# 5_ButtonsAndLeds.net
KiCad netlist of a schematic drawn in Altium Designer
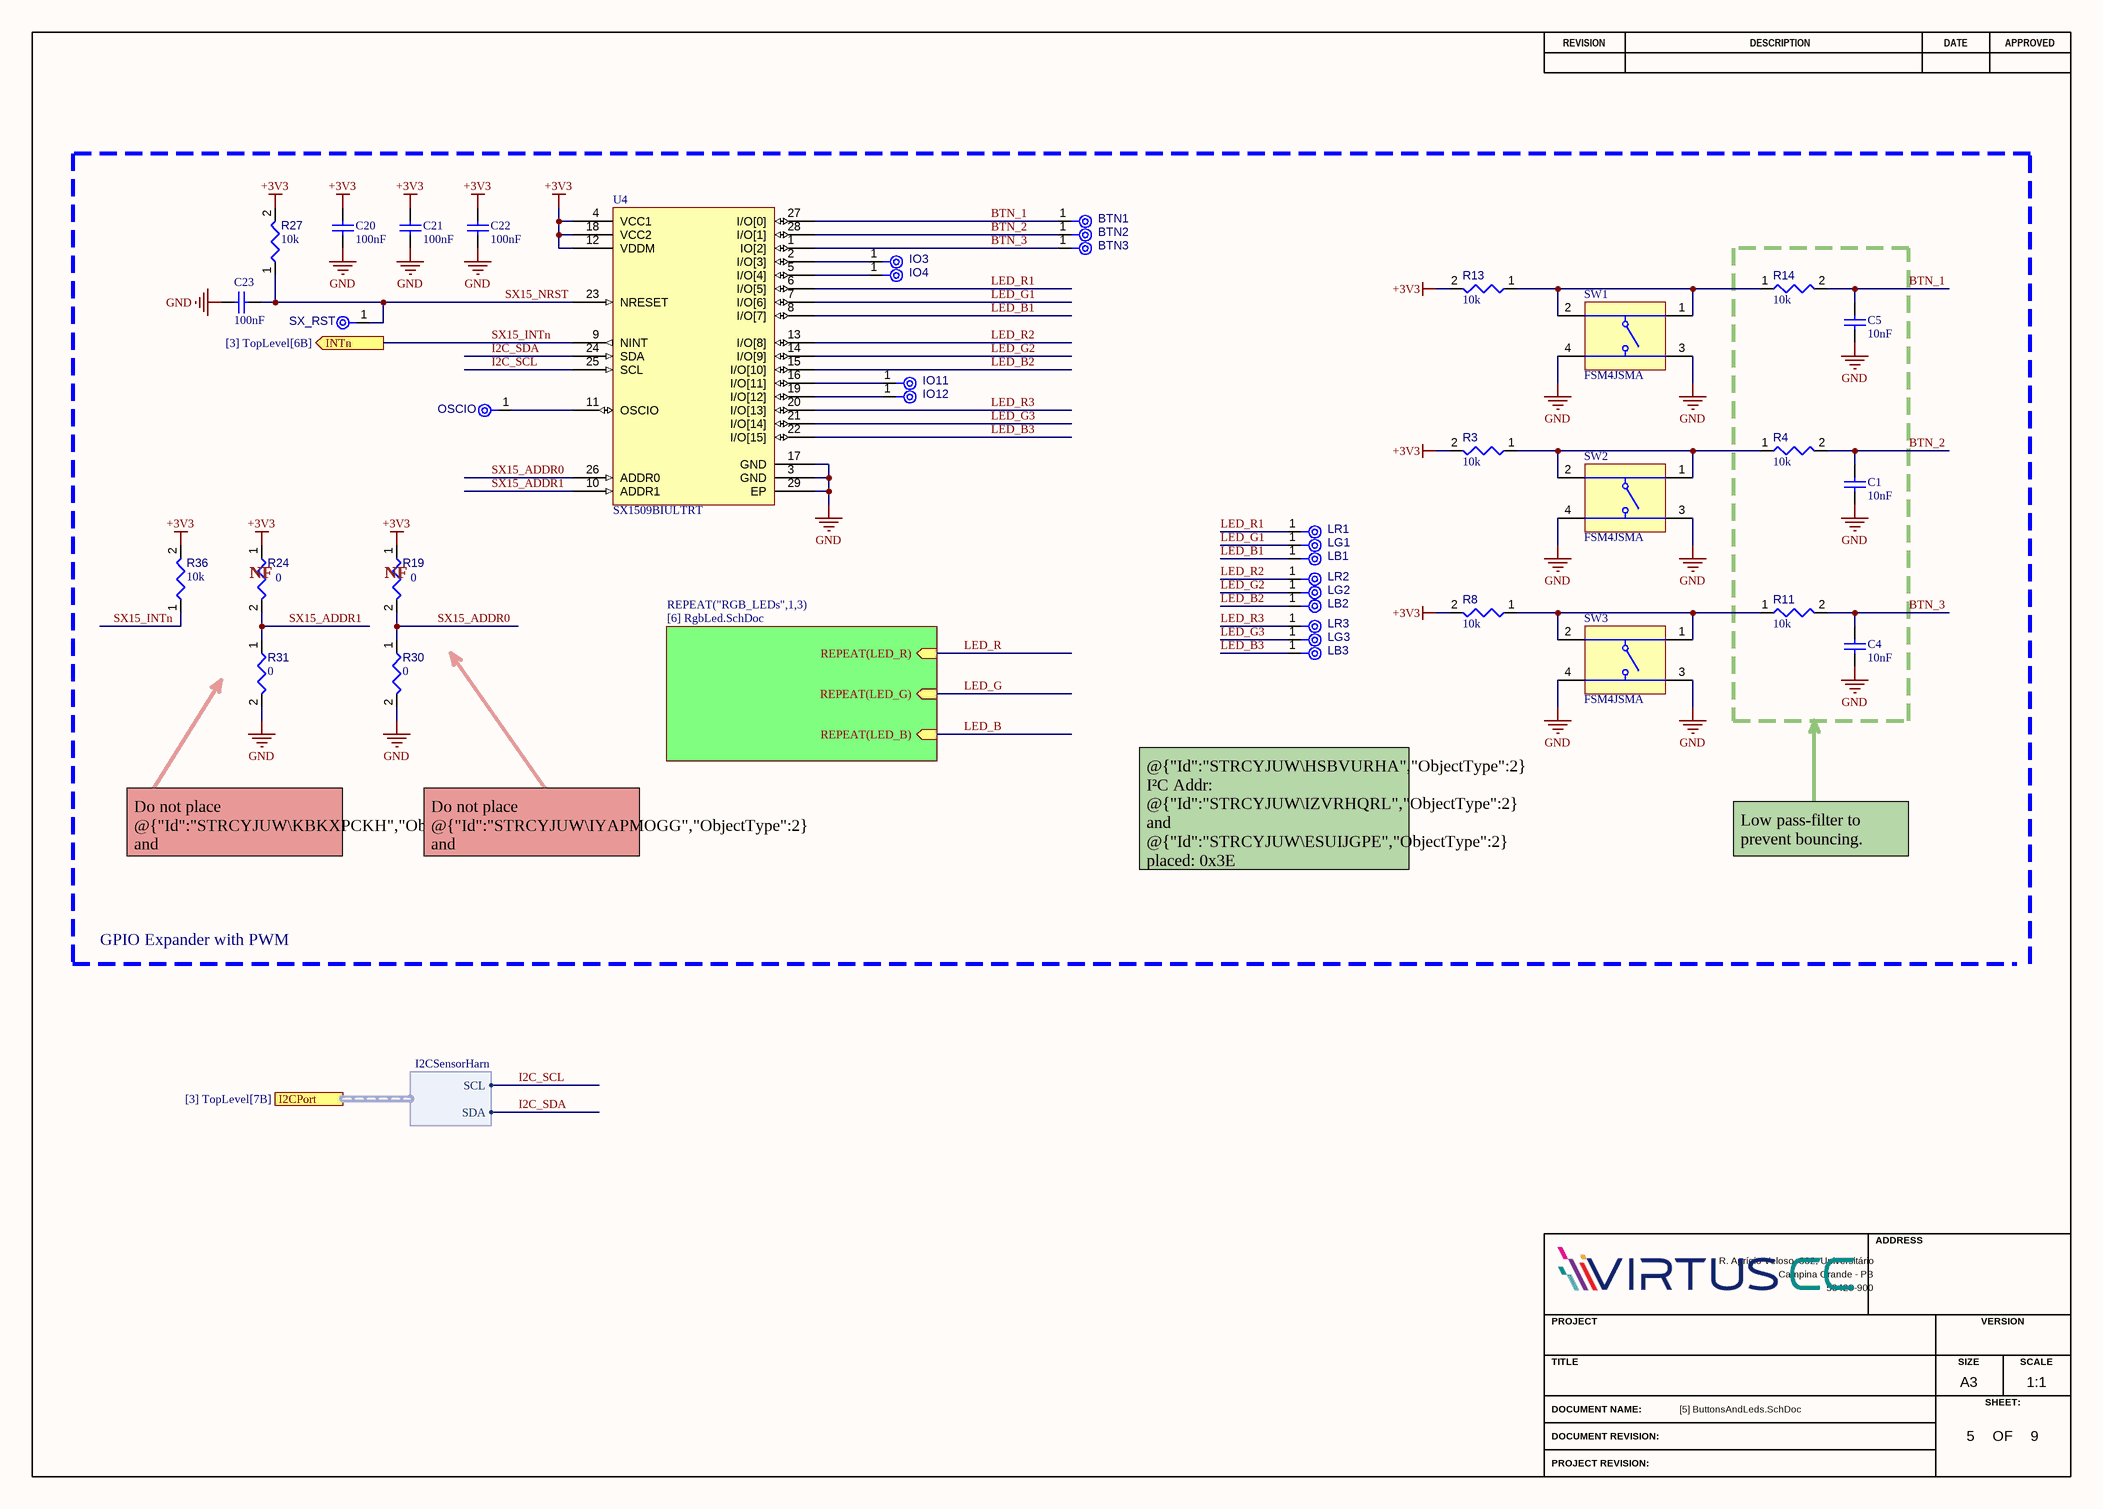
[diagram p0: [5] ButtonsAndLeds.SchDoc]

(export (version "E")
  (design (tool "Eeschema 10.0.6"))
  (components
    (comp (ref "BTN1")
      (value "TPAD6R")
      (footprint "TP06R")
      (description "0.6mm round")
      (libsource (lib "UFCG - Universidade Federal de Campina Grande") (part "CMP-001-0001-4"))
    )
    (comp (ref "BTN2")
      (value "TPAD6R")
      (footprint "TP06R")
      (description "0.6mm round")
      (libsource (lib "UFCG - Universidade Federal de Campina Grande") (part "CMP-001-0001-4"))
    )
    (comp (ref "BTN3")
      (value "TPAD6R")
      (footprint "TP06R")
      (description "0.6mm round")
      (libsource (lib "UFCG - Universidade Federal de Campina Grande") (part "CMP-001-0001-4"))
    )
    (comp (ref "C1")
      (value "10nF")
      (footprint "CAPC0603(1608)100_L")
      (description "Multilayer Ceramic Capacitor, 0.01 uF, 50 V, ± 10%, X7R, 0603 [1608 Metric]")
      (fields (field (name "VOLTAGE") "50V") (field (name "TOLERANCE") "10%"))
      (libsource (lib "UFCG - Universidade Federal de Campina Grande") (part "CAP"))
    )
    (comp (ref "C4")
      (value "10nF")
      (footprint "CAPC0603(1608)100_L")
      (description "Multilayer Ceramic Capacitor, 0.01 uF, 50 V, ± 10%, X7R, 0603 [1608 Metric]")
      (fields (field (name "VOLTAGE") "50V") (field (name "TOLERANCE") "10%"))
      (libsource (lib "UFCG - Universidade Federal de Campina Grande") (part "CAP"))
    )
    (comp (ref "C5")
      (value "10nF")
      (footprint "CAPC0603(1608)100_L")
      (description "Multilayer Ceramic Capacitor, 0.01 uF, 50 V, ± 10%, X7R, 0603 [1608 Metric]")
      (fields (field (name "VOLTAGE") "50V") (field (name "TOLERANCE") "10%"))
      (libsource (lib "UFCG - Universidade Federal de Campina Grande") (part "CAP"))
    )
    (comp (ref "C20")
      (value "100nF")
      (footprint "CAPC0603(1608)100_L")
      (description "Multilayer Ceramic Capacitor, 0.1 uF, 16 V, ± 20%, X7R, 0603 [1608 Metric]")
      (fields (field (name "TOLERANCE") "20%") (field (name "Comment") "VJ0603Y104MXJCW1BC"))
      (libsource (lib "UFCG - Universidade Federal de Campina Grande") (part "CAP"))
    )
    (comp (ref "C21")
      (value "100nF")
      (footprint "CAPC0603(1608)100_L")
      (description "Multilayer Ceramic Capacitor, 0.1 uF, 16 V, ± 20%, X7R, 0603 [1608 Metric]")
      (fields (field (name "TOLERANCE") "20%") (field (name "Comment") "VJ0603Y104MXJCW1BC"))
      (libsource (lib "UFCG - Universidade Federal de Campina Grande") (part "CAP"))
    )
    (comp (ref "C22")
      (value "100nF")
      (footprint "CAPC0603(1608)100_L")
      (description "Multilayer Ceramic Capacitor, 0.1 uF, 16 V, ± 20%, X7R, 0603 [1608 Metric]")
      (fields (field (name "TOLERANCE") "20%") (field (name "Comment") "VJ0603Y104MXJCW1BC"))
      (libsource (lib "UFCG - Universidade Federal de Campina Grande") (part "CAP"))
    )
    (comp (ref "C23")
      (value "100nF")
      (footprint "CAPC0603(1608)100_L")
      (description "Multilayer Ceramic Capacitor, 0.1 uF, 16 V, ± 20%, X7R, 0603 [1608 Metric]")
      (fields (field (name "TOLERANCE") "20%") (field (name "Comment") "VJ0603Y104MXJCW1BC"))
      (libsource (lib "UFCG - Universidade Federal de Campina Grande") (part "CAP"))
    )
    (comp (ref "IO3")
      (value "TPAD6R")
      (footprint "TP06R")
      (description "0.6mm round")
      (libsource (lib "UFCG - Universidade Federal de Campina Grande") (part "CMP-001-0001-4"))
    )
    (comp (ref "IO4")
      (value "TPAD6R")
      (footprint "TP06R")
      (description "0.6mm round")
      (libsource (lib "UFCG - Universidade Federal de Campina Grande") (part "CMP-001-0001-4"))
    )
    (comp (ref "IO11")
      (value "TPAD6R")
      (footprint "TP06R")
      (description "0.6mm round")
      (libsource (lib "UFCG - Universidade Federal de Campina Grande") (part "CMP-001-0001-4"))
    )
    (comp (ref "IO12")
      (value "TPAD6R")
      (footprint "TP06R")
      (description "0.6mm round")
      (libsource (lib "UFCG - Universidade Federal de Campina Grande") (part "CMP-001-0001-4"))
    )
    (comp (ref "LB1")
      (value "TPAD6R")
      (footprint "TP06R")
      (description "0.6mm round")
      (libsource (lib "UFCG - Universidade Federal de Campina Grande") (part "CMP-001-0001-4"))
    )
    (comp (ref "LB2")
      (value "TPAD6R")
      (footprint "TP06R")
      (description "0.6mm round")
      (libsource (lib "UFCG - Universidade Federal de Campina Grande") (part "CMP-001-0001-4"))
    )
    (comp (ref "LB3")
      (value "TPAD6R")
      (footprint "TP06R")
      (description "0.6mm round")
      (libsource (lib "UFCG - Universidade Federal de Campina Grande") (part "CMP-001-0001-4"))
    )
    (comp (ref "LG1")
      (value "TPAD6R")
      (footprint "TP06R")
      (description "0.6mm round")
      (libsource (lib "UFCG - Universidade Federal de Campina Grande") (part "CMP-001-0001-4"))
    )
    (comp (ref "LG2")
      (value "TPAD6R")
      (footprint "TP06R")
      (description "0.6mm round")
      (libsource (lib "UFCG - Universidade Federal de Campina Grande") (part "CMP-001-0001-4"))
    )
    (comp (ref "LG3")
      (value "TPAD6R")
      (footprint "TP06R")
      (description "0.6mm round")
      (libsource (lib "UFCG - Universidade Federal de Campina Grande") (part "CMP-001-0001-4"))
    )
    (comp (ref "LR1")
      (value "TPAD6R")
      (footprint "TP06R")
      (description "0.6mm round")
      (libsource (lib "UFCG - Universidade Federal de Campina Grande") (part "CMP-001-0001-4"))
    )
    (comp (ref "LR2")
      (value "TPAD6R")
      (footprint "TP06R")
      (description "0.6mm round")
      (libsource (lib "UFCG - Universidade Federal de Campina Grande") (part "CMP-001-0001-4"))
    )
    (comp (ref "LR3")
      (value "TPAD6R")
      (footprint "TP06R")
      (description "0.6mm round")
      (libsource (lib "UFCG - Universidade Federal de Campina Grande") (part "CMP-001-0001-4"))
    )
    (comp (ref "OSCIO")
      (value "TPAD6R")
      (footprint "TP06R")
      (description "0.6mm round")
      (libsource (lib "UFCG - Universidade Federal de Campina Grande") (part "CMP-001-0001-4"))
    )
    (comp (ref "R3")
      (value "10k")
      (footprint "RESC0603(1608)_L")
      (description "Chip Resistor, 10 KOhm, +/- 1%, 01 W, -55 to 155 degC, 0603 (1608 Metric)")
      (fields (field (name "POWER") "100mW") (field (name "TOLERANCE") "1%"))
      (libsource (lib "UFCG - Universidade Federal de Campina Grande") (part "RES-2"))
    )
    (comp (ref "R4")
      (value "10k")
      (footprint "RESC0603(1608)_L")
      (description "Chip Resistor, 10 KOhm, +/- 1%, 01 W, -55 to 155 degC, 0603 (1608 Metric)")
      (fields (field (name "POWER") "100mW") (field (name "TOLERANCE") "1%"))
      (libsource (lib "UFCG - Universidade Federal de Campina Grande") (part "RES-2"))
    )
    (comp (ref "R8")
      (value "10k")
      (footprint "RESC0603(1608)_L")
      (description "Chip Resistor, 10 KOhm, +/- 1%, 01 W, -55 to 155 degC, 0603 (1608 Metric)")
      (fields (field (name "POWER") "100mW") (field (name "TOLERANCE") "1%"))
      (libsource (lib "UFCG - Universidade Federal de Campina Grande") (part "RES-2"))
    )
    (comp (ref "R11")
      (value "10k")
      (footprint "RESC0603(1608)_L")
      (description "Chip Resistor, 10 KOhm, +/- 1%, 01 W, -55 to 155 degC, 0603 (1608 Metric)")
      (fields (field (name "POWER") "100mW") (field (name "TOLERANCE") "1%"))
      (libsource (lib "UFCG - Universidade Federal de Campina Grande") (part "RES-2"))
    )
    (comp (ref "R13")
      (value "10k")
      (footprint "RESC0603(1608)_L")
      (description "Chip Resistor, 10 KOhm, +/- 1%, 01 W, -55 to 155 degC, 0603 (1608 Metric)")
      (fields (field (name "POWER") "100mW") (field (name "TOLERANCE") "1%"))
      (libsource (lib "UFCG - Universidade Federal de Campina Grande") (part "RES-2"))
    )
    (comp (ref "R14")
      (value "10k")
      (footprint "RESC0603(1608)_L")
      (description "Chip Resistor, 10 KOhm, +/- 1%, 01 W, -55 to 155 degC, 0603 (1608 Metric)")
      (fields (field (name "POWER") "100mW") (field (name "TOLERANCE") "1%"))
      (libsource (lib "UFCG - Universidade Federal de Campina Grande") (part "RES-2"))
    )
    (comp (ref "R19")
      (value "0")
      (footprint "RESC0603(1608)_L")
      (description "Chip Resistor, 0 Ohm, 0.1 W, -55 to 155 degC, 0603 (1608 Metric)")
      (fields (field (name "TOLERANCE") "5%") (field (name "POWER") "100mW"))
      (libsource (lib "UFCG - Universidade Federal de Campina Grande") (part "RES-2"))
    )
    (comp (ref "R24")
      (value "0")
      (footprint "RESC0603(1608)_L")
      (description "Chip Resistor, 0 Ohm, 0.1 W, -55 to 155 degC, 0603 (1608 Metric)")
      (fields (field (name "TOLERANCE") "5%") (field (name "POWER") "100mW"))
      (libsource (lib "UFCG - Universidade Federal de Campina Grande") (part "RES-2"))
    )
    (comp (ref "R27")
      (value "10k")
      (footprint "RESC0603(1608)_L")
      (description "Chip Resistor, 10 KOhm, +/- 1%, 01 W, -55 to 155 degC, 0603 (1608 Metric)")
      (fields (field (name "POWER") "100mW") (field (name "TOLERANCE") "1%"))
      (libsource (lib "UFCG - Universidade Federal de Campina Grande") (part "RES-2"))
    )
    (comp (ref "R30")
      (value "0")
      (footprint "RESC0603(1608)_L")
      (description "Chip Resistor, 0 Ohm, 0.1 W, -55 to 155 degC, 0603 (1608 Metric)")
      (fields (field (name "TOLERANCE") "5%") (field (name "POWER") "100mW"))
      (libsource (lib "UFCG - Universidade Federal de Campina Grande") (part "RES-2"))
    )
    (comp (ref "R31")
      (value "0")
      (footprint "RESC0603(1608)_L")
      (description "Chip Resistor, 0 Ohm, 0.1 W, -55 to 155 degC, 0603 (1608 Metric)")
      (fields (field (name "TOLERANCE") "5%") (field (name "POWER") "100mW"))
      (libsource (lib "UFCG - Universidade Federal de Campina Grande") (part "RES-2"))
    )
    (comp (ref "R36")
      (value "10k")
      (footprint "RESC0603(1608)_L")
      (description "Chip Resistor, 10 KOhm, +/- 1%, 01 W, -55 to 155 degC, 0603 (1608 Metric)")
      (fields (field (name "POWER") "100mW") (field (name "TOLERANCE") "1%"))
      (libsource (lib "UFCG - Universidade Federal de Campina Grande") (part "RES-2"))
    )
    (comp (ref "SW1")
      (value "FSM4JSMA")
      (footprint "TECO-FSM4JSMA_V")
      (description "Switch Tactile OFF (ON) SPST Round Button Gull Wing 0.05A 12VDC 1.57N SMD Loose Piece")
      (libsource (lib "UFCG - Universidade Federal de Campina Grande") (part "SW-SPST-4_A"))
    )
    (comp (ref "SW2")
      (value "FSM4JSMA")
      (footprint "TECO-FSM4JSMA_V")
      (description "Switch Tactile OFF (ON) SPST Round Button Gull Wing 0.05A 12VDC 1.57N SMD Loose Piece")
      (libsource (lib "UFCG - Universidade Federal de Campina Grande") (part "SW-SPST-4_A"))
    )
    (comp (ref "SW3")
      (value "FSM4JSMA")
      (footprint "TECO-FSM4JSMA_V")
      (description "Switch Tactile OFF (ON) SPST Round Button Gull Wing 0.05A 12VDC 1.57N SMD Loose Piece")
      (libsource (lib "UFCG - Universidade Federal de Campina Grande") (part "SW-SPST-4_A"))
    )
    (comp (ref "SX_RST")
      (value "TPAD6R")
      (footprint "TP06R")
      (description "0.6mm round")
      (libsource (lib "UFCG - Universidade Federal de Campina Grande") (part "CMP-001-0001-4"))
    )
    (comp (ref "U4")
      (value "SX1509BIULTRT")
      (footprint "QFN40P410X410X60_HS-29N")
      (description "IC Gpio Expander I2C 16CH 28QFN / I2C Interface 5.5V 28-PIN Qfn-ut Ep T/r")
      (libsource (lib "UFCG - Universidade Federal de Campina Grande") (part "New symbol 1"))
    )
  )
  (nets
    (net (code "2") (name "+3V3") (class "Default")
      (node (ref "C20") (pin "1") (pinfunction "1_1") (pintype "passive"))
      (node (ref "C21") (pin "1") (pinfunction "1_1") (pintype "passive"))
      (node (ref "C22") (pin "1") (pinfunction "1_1") (pintype "passive"))
      (node (ref "R13") (pin "2") (pinfunction "2_2") (pintype "passive"))
      (node (ref "R19") (pin "1") (pinfunction "1_1") (pintype "passive"))
      (node (ref "R24") (pin "1") (pinfunction "1_1") (pintype "passive"))
      (node (ref "R27") (pin "2") (pinfunction "2_2") (pintype "passive"))
      (node (ref "R3") (pin "2") (pinfunction "2_2") (pintype "passive"))
      (node (ref "R36") (pin "2") (pinfunction "2_2") (pintype "passive"))
      (node (ref "R8") (pin "2") (pinfunction "2_2") (pintype "passive"))
      (node (ref "U4") (pin "12") (pinfunction "VDDM_12") (pintype "power_in"))
      (node (ref "U4") (pin "18") (pinfunction "VCC2_18") (pintype "power_in"))
      (node (ref "U4") (pin "4") (pinfunction "VCC1_4") (pintype "power_in"))
    )
    (net (code "3") (name "/BTN_1") (class "Default")
      (node (ref "BTN1") (pin "1") (pinfunction "TP_1") (pintype "passive"))
      (node (ref "C5") (pin "2") (pinfunction "2_2") (pintype "passive"))
      (node (ref "R14") (pin "2") (pinfunction "2_2") (pintype "passive"))
      (node (ref "U4") (pin "27") (pinfunction "I/O[0]_27") (pintype "bidirectional"))
    )
    (net (code "4") (name "/BTN_2") (class "Default")
      (node (ref "BTN2") (pin "1") (pinfunction "TP_1") (pintype "passive"))
      (node (ref "C1") (pin "2") (pinfunction "2_2") (pintype "passive"))
      (node (ref "R4") (pin "2") (pinfunction "2_2") (pintype "passive"))
      (node (ref "U4") (pin "28") (pinfunction "I/O[1]_28") (pintype "bidirectional"))
    )
    (net (code "5") (name "/BTN_3") (class "Default")
      (node (ref "BTN3") (pin "1") (pinfunction "TP_1") (pintype "passive"))
      (node (ref "C4") (pin "2") (pinfunction "2_2") (pintype "passive"))
      (node (ref "R11") (pin "2") (pinfunction "2_2") (pintype "passive"))
      (node (ref "U4") (pin "1") (pinfunction "IO[2]_1") (pintype "bidirectional"))
    )
    (net (code "6") (name "/I2C_SCL") (class "Default")
      (node (ref "U4") (pin "25") (pinfunction "SCL_25") (pintype "input"))
    )
    (net (code "7") (name "/I2C_SDA") (class "Default")
      (node (ref "U4") (pin "24") (pinfunction "SDA_24") (pintype "input"))
    )
    (net (code "9") (name "/LED_B1") (class "Default")
      (node (ref "LB1") (pin "1") (pinfunction "TP_1") (pintype "passive"))
      (node (ref "U4") (pin "8") (pinfunction "I/O[7]_8") (pintype "bidirectional"))
    )
    (net (code "10") (name "/LED_B2") (class "Default")
      (node (ref "LB2") (pin "1") (pinfunction "TP_1") (pintype "passive"))
      (node (ref "U4") (pin "15") (pinfunction "I/O[10]_15") (pintype "bidirectional"))
    )
    (net (code "11") (name "/LED_B3") (class "Default")
      (node (ref "LB3") (pin "1") (pinfunction "TP_1") (pintype "passive"))
      (node (ref "U4") (pin "22") (pinfunction "I/O[15]_22") (pintype "bidirectional"))
    )
    (net (code "13") (name "/LED_G1") (class "Default")
      (node (ref "LG1") (pin "1") (pinfunction "TP_1") (pintype "passive"))
      (node (ref "U4") (pin "7") (pinfunction "I/O[6]_7") (pintype "bidirectional"))
    )
    (net (code "14") (name "/LED_G2") (class "Default")
      (node (ref "LG2") (pin "1") (pinfunction "TP_1") (pintype "passive"))
      (node (ref "U4") (pin "14") (pinfunction "I/O[9]_14") (pintype "bidirectional"))
    )
    (net (code "15") (name "/LED_G3") (class "Default")
      (node (ref "LG3") (pin "1") (pinfunction "TP_1") (pintype "passive"))
      (node (ref "U4") (pin "21") (pinfunction "I/O[14]_21") (pintype "bidirectional"))
    )
    (net (code "17") (name "/LED_R1") (class "Default")
      (node (ref "LR1") (pin "1") (pinfunction "TP_1") (pintype "passive"))
      (node (ref "U4") (pin "6") (pinfunction "I/O[5]_6") (pintype "bidirectional"))
    )
    (net (code "18") (name "/LED_R2") (class "Default")
      (node (ref "LR2") (pin "1") (pinfunction "TP_1") (pintype "passive"))
      (node (ref "U4") (pin "13") (pinfunction "I/O[8]_13") (pintype "bidirectional"))
    )
    (net (code "19") (name "/LED_R3") (class "Default")
      (node (ref "LR3") (pin "1") (pinfunction "TP_1") (pintype "passive"))
      (node (ref "U4") (pin "20") (pinfunction "I/O[13]_20") (pintype "bidirectional"))
    )
    (net (code "20") (name "/SX15_ADDR0") (class "Default")
      (node (ref "R19") (pin "2") (pinfunction "2_2") (pintype "passive"))
      (node (ref "R30") (pin "1") (pinfunction "1_1") (pintype "passive"))
      (node (ref "U4") (pin "26") (pinfunction "ADDR0_26") (pintype "input"))
    )
    (net (code "21") (name "/SX15_ADDR1") (class "Default")
      (node (ref "R24") (pin "2") (pinfunction "2_2") (pintype "passive"))
      (node (ref "R31") (pin "1") (pinfunction "1_1") (pintype "passive"))
      (node (ref "U4") (pin "10") (pinfunction "ADDR1_10") (pintype "input"))
    )
    (net (code "22") (name "/SX15_INTn") (class "Default")
      (node (ref "R36") (pin "1") (pinfunction "1_1") (pintype "passive"))
      (node (ref "U4") (pin "9") (pinfunction "NINT_9") (pintype "output"))
    )
    (net (code "23") (name "/SX15_NRST") (class "Default")
      (node (ref "C23") (pin "2") (pinfunction "2_2") (pintype "passive"))
      (node (ref "R27") (pin "1") (pinfunction "1_1") (pintype "passive"))
      (node (ref "SX_RST") (pin "1") (pinfunction "TP_1") (pintype "passive"))
      (node (ref "U4") (pin "23") (pinfunction "NRESET_23") (pintype "input"))
    )
    (net (code "25") (name "GND") (class "Default")
      (node (ref "C1") (pin "1") (pinfunction "1_1") (pintype "passive"))
      (node (ref "C20") (pin "2") (pinfunction "2_2") (pintype "passive"))
      (node (ref "C21") (pin "2") (pinfunction "2_2") (pintype "passive"))
      (node (ref "C22") (pin "2") (pinfunction "2_2") (pintype "passive"))
      (node (ref "C23") (pin "1") (pinfunction "1_1") (pintype "passive"))
      (node (ref "C4") (pin "1") (pinfunction "1_1") (pintype "passive"))
      (node (ref "C5") (pin "1") (pinfunction "1_1") (pintype "passive"))
      (node (ref "R30") (pin "2") (pinfunction "2_2") (pintype "passive"))
      (node (ref "R31") (pin "2") (pinfunction "2_2") (pintype "passive"))
      (node (ref "SW1") (pin "3") (pinfunction "3_3") (pintype "passive"))
      (node (ref "SW1") (pin "4") (pinfunction "4_4") (pintype "passive"))
      (node (ref "SW2") (pin "3") (pinfunction "3_3") (pintype "passive"))
      (node (ref "SW2") (pin "4") (pinfunction "4_4") (pintype "passive"))
      (node (ref "SW3") (pin "3") (pinfunction "3_3") (pintype "passive"))
      (node (ref "SW3") (pin "4") (pinfunction "4_4") (pintype "passive"))
      (node (ref "U4") (pin "17") (pinfunction "GND_17") (pintype "power_in"))
      (node (ref "U4") (pin "29") (pinfunction "EP_29") (pintype "power_in"))
      (node (ref "U4") (pin "3") (pinfunction "GND_3") (pintype "power_in"))
    )
    (net (code "26") (name "Net-(IO3-TP)") (class "Default")
      (node (ref "IO3") (pin "1") (pinfunction "TP_1") (pintype "passive"))
      (node (ref "U4") (pin "2") (pinfunction "I/O[3]_2") (pintype "bidirectional"))
    )
    (net (code "27") (name "Net-(IO4-TP)") (class "Default")
      (node (ref "IO4") (pin "1") (pinfunction "TP_1") (pintype "passive"))
      (node (ref "U4") (pin "5") (pinfunction "I/O[4]_5") (pintype "bidirectional"))
    )
    (net (code "28") (name "Net-(IO11-TP)") (class "Default")
      (node (ref "IO11") (pin "1") (pinfunction "TP_1") (pintype "passive"))
      (node (ref "U4") (pin "16") (pinfunction "I/O[11]_16") (pintype "bidirectional"))
    )
    (net (code "29") (name "Net-(IO12-TP)") (class "Default")
      (node (ref "IO12") (pin "1") (pinfunction "TP_1") (pintype "passive"))
      (node (ref "U4") (pin "19") (pinfunction "I/O[12]_19") (pintype "bidirectional"))
    )
    (net (code "30") (name "Net-(OSCIO-TP)") (class "Default")
      (node (ref "OSCIO") (pin "1") (pinfunction "TP_1") (pintype "passive"))
      (node (ref "U4") (pin "11") (pinfunction "OSCIO_11") (pintype "bidirectional"))
    )
    (net (code "31") (name "Net-(R3-Pad1)") (class "Default")
      (node (ref "R3") (pin "1") (pinfunction "1_1") (pintype "passive"))
      (node (ref "R4") (pin "1") (pinfunction "1_1") (pintype "passive"))
      (node (ref "SW2") (pin "1") (pinfunction "1_1") (pintype "passive"))
      (node (ref "SW2") (pin "2") (pinfunction "2_2") (pintype "passive"))
    )
    (net (code "32") (name "Net-(R11-Pad1)") (class "Default")
      (node (ref "R11") (pin "1") (pinfunction "1_1") (pintype "passive"))
      (node (ref "R8") (pin "1") (pinfunction "1_1") (pintype "passive"))
      (node (ref "SW3") (pin "1") (pinfunction "1_1") (pintype "passive"))
      (node (ref "SW3") (pin "2") (pinfunction "2_2") (pintype "passive"))
    )
    (net (code "33") (name "Net-(R13-Pad1)") (class "Default")
      (node (ref "R13") (pin "1") (pinfunction "1_1") (pintype "passive"))
      (node (ref "R14") (pin "1") (pinfunction "1_1") (pintype "passive"))
      (node (ref "SW1") (pin "1") (pinfunction "1_1") (pintype "passive"))
      (node (ref "SW1") (pin "2") (pinfunction "2_2") (pintype "passive"))
    )
  )
)
